# lv_controller_power.net
KiCad netlist of a schematic drawn in Altium Designer
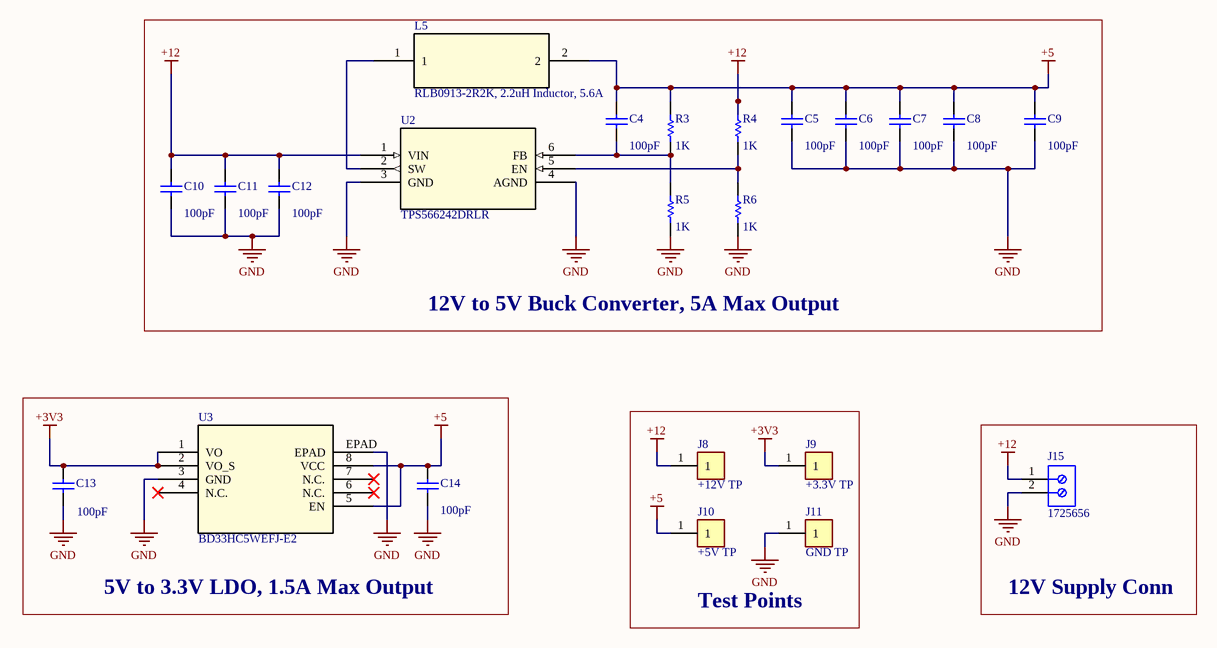
[diagram p0: lv_controller_power.SchDoc]

(export (version "E")
  (design (tool "Eeschema 10.0.6"))
  (components
    (comp (ref "C4")
      (value "100pF")
      (footprint "C0805")
      (description "Capacitor")
      (fields (field (name "Comment") "Cap") (field (name "PUBLISHER") "Altium Limited"))
      (libsource (lib "Miscellaneous Devices") (part "Cap"))
    )
    (comp (ref "C5")
      (value "100pF")
      (footprint "C0805")
      (description "Capacitor")
      (fields (field (name "Comment") "Cap") (field (name "PUBLISHER") "Altium Limited"))
      (libsource (lib "Miscellaneous Devices") (part "Cap"))
    )
    (comp (ref "C6")
      (value "100pF")
      (footprint "C0805")
      (description "Capacitor")
      (fields (field (name "Comment") "Cap") (field (name "PUBLISHER") "Altium Limited"))
      (libsource (lib "Miscellaneous Devices") (part "Cap"))
    )
    (comp (ref "C7")
      (value "100pF")
      (footprint "C0805")
      (description "Capacitor")
      (fields (field (name "Comment") "Cap") (field (name "PUBLISHER") "Altium Limited"))
      (libsource (lib "Miscellaneous Devices") (part "Cap"))
    )
    (comp (ref "C8")
      (value "100pF")
      (footprint "C0805")
      (description "Capacitor")
      (fields (field (name "Comment") "Cap") (field (name "PUBLISHER") "Altium Limited"))
      (libsource (lib "Miscellaneous Devices") (part "Cap"))
    )
    (comp (ref "C9")
      (value "100pF")
      (footprint "C0805")
      (description "Capacitor")
      (fields (field (name "Comment") "Cap") (field (name "PUBLISHER") "Altium Limited"))
      (libsource (lib "Miscellaneous Devices") (part "Cap"))
    )
    (comp (ref "C10")
      (value "100pF")
      (footprint "C0805")
      (description "Capacitor")
      (fields (field (name "Comment") "Cap") (field (name "PUBLISHER") "Altium Limited"))
      (libsource (lib "Miscellaneous Devices") (part "Cap"))
    )
    (comp (ref "C11")
      (value "100pF")
      (footprint "C0805")
      (description "Capacitor")
      (fields (field (name "Comment") "Cap") (field (name "PUBLISHER") "Altium Limited"))
      (libsource (lib "Miscellaneous Devices") (part "Cap"))
    )
    (comp (ref "C12")
      (value "100pF")
      (footprint "C0805")
      (description "Capacitor")
      (fields (field (name "Comment") "Cap") (field (name "PUBLISHER") "Altium Limited"))
      (libsource (lib "Miscellaneous Devices") (part "Cap"))
    )
    (comp (ref "C13")
      (value "100pF")
      (footprint "C0805")
      (description "Capacitor")
      (fields (field (name "Comment") "Cap") (field (name "PUBLISHER") "Altium Limited"))
      (libsource (lib "Miscellaneous Devices") (part "Cap"))
    )
    (comp (ref "C14")
      (value "100pF")
      (footprint "C0805")
      (description "Capacitor")
      (fields (field (name "Comment") "Cap") (field (name "PUBLISHER") "Altium Limited"))
      (libsource (lib "Miscellaneous Devices") (part "Cap"))
    )
    (comp (ref "J8")
      (value "+12V TP")
      (footprint "KEYSTONE_5000")
      (fields (field (name "MP") "5000") (field (name "MF") "Keystone"))
      (libsource (lib "lv_controller_lib") (part "5000"))
    )
    (comp (ref "J9")
      (value "+3.3V TP")
      (footprint "KEYSTONE_5000")
      (fields (field (name "MP") "5000") (field (name "MF") "Keystone"))
      (libsource (lib "lv_controller_lib") (part "5000"))
    )
    (comp (ref "J10")
      (value "+5V TP")
      (footprint "KEYSTONE_5000")
      (fields (field (name "MP") "5000") (field (name "MF") "Keystone"))
      (libsource (lib "lv_controller_lib") (part "5000"))
    )
    (comp (ref "J11")
      (value "GND TP")
      (footprint "KEYSTONE_5000")
      (fields (field (name "MP") "5000") (field (name "MF") "Keystone"))
      (libsource (lib "lv_controller_lib") (part "5000"))
    )
    (comp (ref "J15")
      (value "1725656")
      (footprint "PHOE-1725656-2")
      (description "Male Header, Pitch 2.54 mm, 1 x 2 Position, Height 9 mm, Tail Length 3.5 mm")
      (fields (field (name "MANUFACTURER") "Phoenix Contact"))
      (libsource (lib "Altium Content Vault") (part "CN-1P-F-TB2"))
    )
    (comp (ref "L5")
      (value "RLB0913-2R2K, 2.2uH Inductor, 5.6A")
      (footprint "RLB0913-4R7K_BRN")
      (description "No Description Available")
      (fields
        (field (name "MANUFACTURER_PART_NUMBER") "RLB0913-4R7K")
        (field (name "COPYRIGHT") "Copyright (C) 2022 Ultra Librarian. All rights reserved.")
      )
      (libsource (lib "lv_controller_lib") (part "RLB0913-4R7K"))
    )
    (comp (ref "R3")
      (value "1K")
      (footprint "6-0805_M")
      (description "Resistor")
      (fields (field (name "Comment") "Res1") (field (name "PUBLISHER") "Altium Limited"))
      (libsource (lib "Miscellaneous Devices") (part "Res1"))
    )
    (comp (ref "R4")
      (value "1K")
      (footprint "6-0805_M")
      (description "Resistor")
      (fields (field (name "Comment") "Res1") (field (name "PUBLISHER") "Altium Limited"))
      (libsource (lib "Miscellaneous Devices") (part "Res1"))
    )
    (comp (ref "R5")
      (value "1K")
      (footprint "6-0805_M")
      (description "Resistor")
      (fields (field (name "Comment") "Res1") (field (name "PUBLISHER") "Altium Limited"))
      (libsource (lib "Miscellaneous Devices") (part "Res1"))
    )
    (comp (ref "R6")
      (value "1K")
      (footprint "6-0805_M")
      (description "Resistor")
      (fields (field (name "Comment") "Res1") (field (name "PUBLISHER") "Altium Limited"))
      (libsource (lib "Miscellaneous Devices") (part "Res1"))
    )
    (comp (ref "U2")
      (value "TPS566242DRLR")
      (footprint "SOT5x3_DRL_TEX")
      (description "No Description Available")
      (fields (field (name "COPYRIGHT") "Copyright (C) 2022 Ultra Librarian. All rights reserved."))
      (libsource (lib "lv_controller_lib") (part "TPS566242DRLR"))
    )
    (comp (ref "U3")
      (value "BD33HC5WEFJ-E2")
      (footprint "HTSOP-J8_ROM")
      (description "No Description Available")
      (fields (field (name "COPYRIGHT") "Copyright (C) 2022 Ultra Librarian. All rights reserved."))
      (libsource (lib "lv_controller_lib") (part "BD33HC5WEFJ-E2"))
    )
  )
  (nets
    (net (code "1") (name "+3V3") (class "Default")
      (node (ref "C13") (pin "2") (pinfunction "2_2") (pintype "passive"))
      (node (ref "J9") (pin "1") (pinfunction "1_1") (pintype "passive"))
      (node (ref "U3") (pin "1") (pinfunction "VO_1") (pintype "passive"))
      (node (ref "U3") (pin "2") (pinfunction "VO_S_2") (pintype "passive"))
    )
    (net (code "2") (name "+5") (class "Default")
      (node (ref "C14") (pin "2") (pinfunction "2_2") (pintype "passive"))
      (node (ref "C4") (pin "2") (pinfunction "2_2") (pintype "passive"))
      (node (ref "C5") (pin "2") (pinfunction "2_2") (pintype "passive"))
      (node (ref "C6") (pin "2") (pinfunction "2_2") (pintype "passive"))
      (node (ref "C7") (pin "2") (pinfunction "2_2") (pintype "passive"))
      (node (ref "C8") (pin "2") (pinfunction "2_2") (pintype "passive"))
      (node (ref "C9") (pin "2") (pinfunction "2_2") (pintype "passive"))
      (node (ref "J10") (pin "1") (pinfunction "1_1") (pintype "passive"))
      (node (ref "L5") (pin "2") (pinfunction "2_2") (pintype "passive"))
      (node (ref "R3") (pin "1") (pinfunction "1_1") (pintype "passive"))
      (node (ref "U3") (pin "5") (pinfunction "EN_5") (pintype "passive"))
      (node (ref "U3") (pin "8") (pinfunction "VCC_8") (pintype "power_in"))
    )
    (net (code "3") (name "+12") (class "Default")
      (node (ref "C10") (pin "2") (pinfunction "2_2") (pintype "passive"))
      (node (ref "C11") (pin "2") (pinfunction "2_2") (pintype "passive"))
      (node (ref "C12") (pin "2") (pinfunction "2_2") (pintype "passive"))
      (node (ref "J15") (pin "1") (pinfunction "1_1") (pintype "passive"))
      (node (ref "J8") (pin "1") (pinfunction "1_1") (pintype "passive"))
      (node (ref "R4") (pin "1") (pinfunction "1_1") (pintype "passive"))
      (node (ref "U2") (pin "1") (pinfunction "VIN_1") (pintype "input"))
    )
    (net (code "4") (name "GND") (class "Default")
      (node (ref "C10") (pin "1") (pinfunction "1_1") (pintype "passive"))
      (node (ref "C11") (pin "1") (pinfunction "1_1") (pintype "passive"))
      (node (ref "C12") (pin "1") (pinfunction "1_1") (pintype "passive"))
      (node (ref "C13") (pin "1") (pinfunction "1_1") (pintype "passive"))
      (node (ref "C14") (pin "1") (pinfunction "1_1") (pintype "passive"))
      (node (ref "C5") (pin "1") (pinfunction "1_1") (pintype "passive"))
      (node (ref "C6") (pin "1") (pinfunction "1_1") (pintype "passive"))
      (node (ref "C7") (pin "1") (pinfunction "1_1") (pintype "passive"))
      (node (ref "C8") (pin "1") (pinfunction "1_1") (pintype "passive"))
      (node (ref "C9") (pin "1") (pinfunction "1_1") (pintype "passive"))
      (node (ref "J11") (pin "1") (pinfunction "1_1") (pintype "passive"))
      (node (ref "J15") (pin "2") (pinfunction "2_2") (pintype "passive"))
      (node (ref "R5") (pin "2") (pinfunction "2_2") (pintype "passive"))
      (node (ref "R6") (pin "2") (pinfunction "2_2") (pintype "passive"))
      (node (ref "U2") (pin "3") (pinfunction "GND_3") (pintype "passive"))
      (node (ref "U2") (pin "4") (pinfunction "AGND_4") (pintype "passive"))
      (node (ref "U3") (pin "3") (pinfunction "GND_3") (pintype "passive"))
      (node (ref "U3") (pin "EPAD") (pinfunction "EPAD_EPAD") (pintype "passive"))
    )
    (net (code "5") (name "Net-(U2-EN)") (class "Default")
      (node (ref "R4") (pin "2") (pinfunction "2_2") (pintype "passive"))
      (node (ref "R6") (pin "1") (pinfunction "1_1") (pintype "passive"))
      (node (ref "U2") (pin "5") (pinfunction "EN_5") (pintype "input"))
    )
    (net (code "6") (name "Net-(U2-FB)") (class "Default")
      (node (ref "C4") (pin "1") (pinfunction "1_1") (pintype "passive"))
      (node (ref "R3") (pin "2") (pinfunction "2_2") (pintype "passive"))
      (node (ref "R5") (pin "1") (pinfunction "1_1") (pintype "passive"))
      (node (ref "U2") (pin "6") (pinfunction "FB_6") (pintype "input"))
    )
    (net (code "7") (name "Net-(U2-SW)") (class "Default")
      (node (ref "L5") (pin "1") (pinfunction "1_1") (pintype "passive"))
      (node (ref "U2") (pin "2") (pinfunction "SW_2") (pintype "output"))
    )
    (net (code "8") (name "unconnected-(U3-N.C.-Pad4)") (class "Default")
      (node (ref "U3") (pin "4") (pinfunction "N.C._4") (pintype "passive+no_connect"))
    )
    (net (code "9") (name "unconnected-(U3-N.C.-Pad6)") (class "Default")
      (node (ref "U3") (pin "6") (pinfunction "N.C._6") (pintype "passive+no_connect"))
    )
    (net (code "10") (name "unconnected-(U3-N.C.-Pad7)") (class "Default")
      (node (ref "U3") (pin "7") (pinfunction "N.C._7") (pintype "passive+no_connect"))
    )
  )
)
